# bms_slave.net
KiCad netlist of a schematic drawn in EAGLE
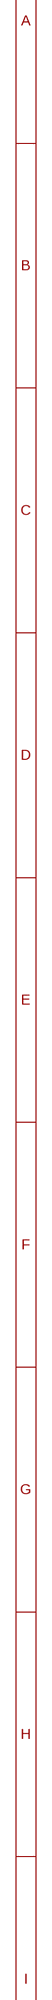
[diagram p0: schematic, sheet 1, part 1 of 2]
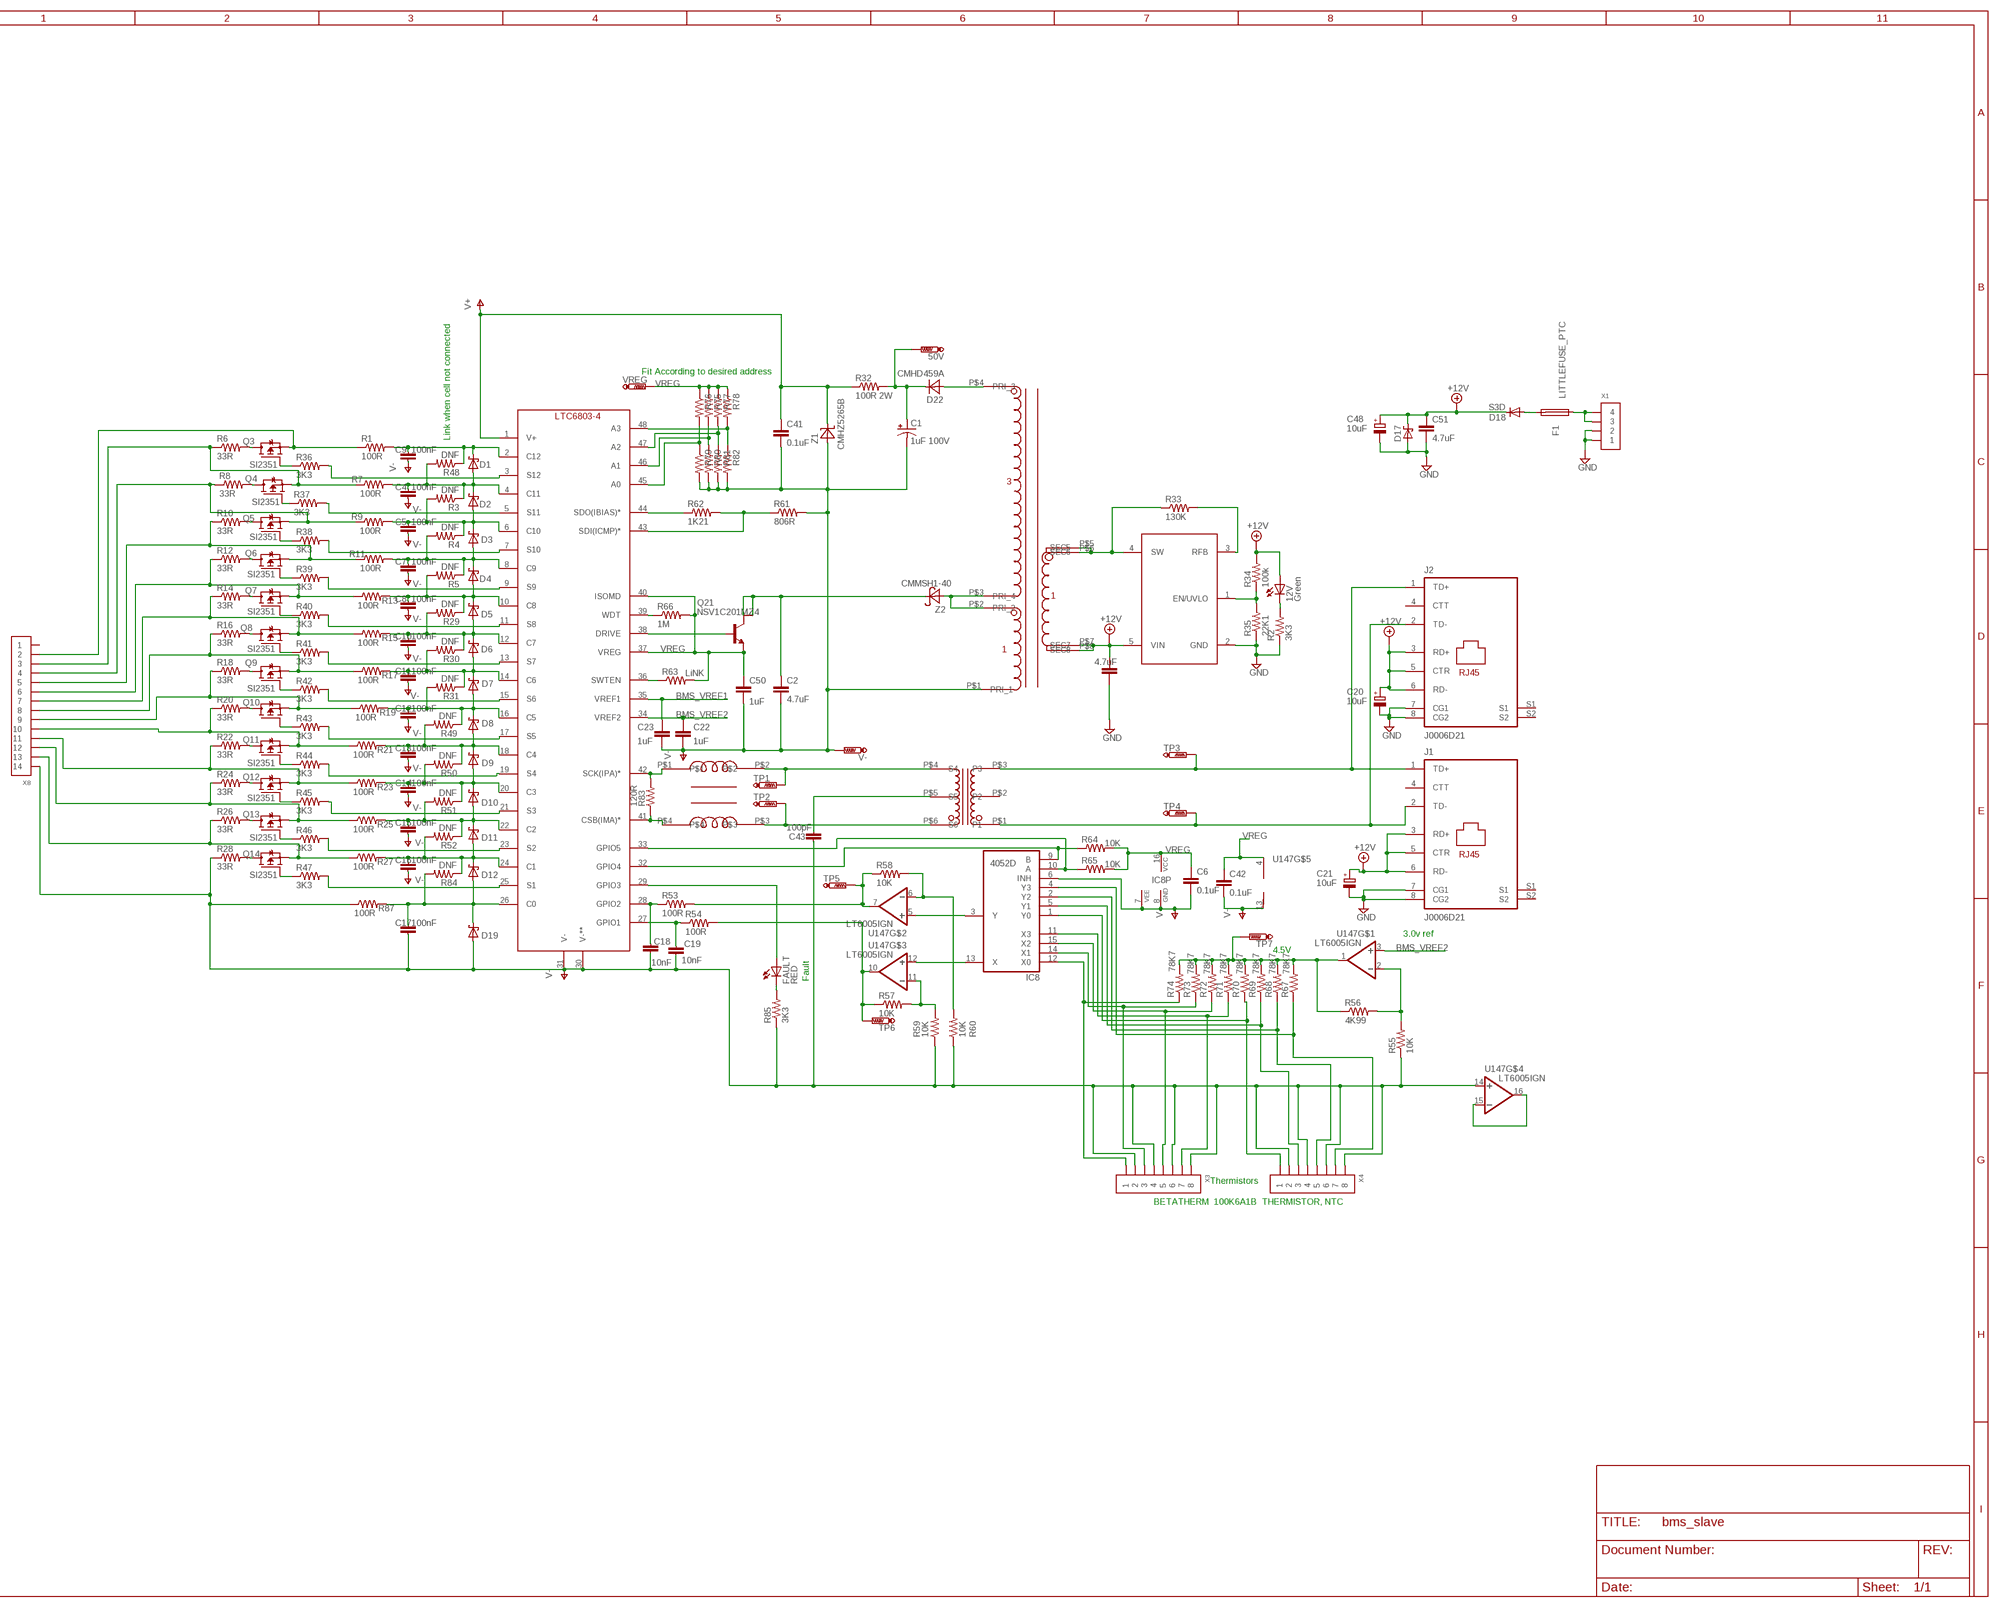
[diagram p1: schematic, sheet 1, part 2 of 2]

(export (version "E")
  (design (tool "Eeschema 10.0.6"))
  (components
    (comp (ref "12V")
      (value "Green")
      (footprint "eagle-import:CHIP-LED0805")
      (libsource (lib "eagle-import") (part "LEDCHIP-LED0805"))
    )
    (comp (ref "50V")
      (value "PTR1PAD1-13")
      (footprint "eagle-import:P1-13")
      (libsource (lib "eagle-import") (part "PTR1PAD1-13"))
    )
    (comp (ref "C1")
      (value "1uF 100V")
      (footprint "eagle-import:SMC_D")
      (libsource (lib "eagle-import") (part "CPOL-USSMCD"))
    )
    (comp (ref "C2")
      (value "4.7uF")
      (footprint "eagle-import:C1206")
      (libsource (lib "eagle-import") (part "C-EUC1206"))
    )
    (comp (ref "C3")
      (value "4.7uF")
      (footprint "eagle-import:C1206")
      (libsource (lib "eagle-import") (part "C-EUC1206"))
    )
    (comp (ref "C4")
      (value "100nF")
      (footprint "eagle-import:C0603@1")
      (libsource (lib "eagle-import") (part "C-EU-SMALL_0603"))
    )
    (comp (ref "C5")
      (value "100nF")
      (footprint "eagle-import:C0603@1")
      (libsource (lib "eagle-import") (part "C-EU-SMALL_0603"))
    )
    (comp (ref "C6")
      (value "0.1uF")
      (footprint "eagle-import:C1206")
      (libsource (lib "eagle-import") (part "C-EUC1206"))
    )
    (comp (ref "C7")
      (value "100nF")
      (footprint "eagle-import:C0603@1")
      (libsource (lib "eagle-import") (part "C-EU-SMALL_0603"))
    )
    (comp (ref "C8")
      (value "100nF")
      (footprint "eagle-import:C0603@1")
      (libsource (lib "eagle-import") (part "C-EU-SMALL_0603"))
    )
    (comp (ref "C9")
      (value "100nF")
      (footprint "eagle-import:C0603@1")
      (libsource (lib "eagle-import") (part "C-EU-SMALL_0603"))
    )
    (comp (ref "C10")
      (value "100nF")
      (footprint "eagle-import:C0603@1")
      (libsource (lib "eagle-import") (part "C-EU-SMALL_0603"))
    )
    (comp (ref "C11")
      (value "100nF")
      (footprint "eagle-import:C0603@1")
      (libsource (lib "eagle-import") (part "C-EU-SMALL_0603"))
    )
    (comp (ref "C12")
      (value "100nF")
      (footprint "eagle-import:C0603@1")
      (libsource (lib "eagle-import") (part "C-EU-SMALL_0603"))
    )
    (comp (ref "C13")
      (value "100nF")
      (footprint "eagle-import:C0603@1")
      (libsource (lib "eagle-import") (part "C-EU-SMALL_0603"))
    )
    (comp (ref "C14")
      (value "100nF")
      (footprint "eagle-import:C0603@1")
      (libsource (lib "eagle-import") (part "C-EU-SMALL_0603"))
    )
    (comp (ref "C15")
      (value "100nF")
      (footprint "eagle-import:C0603@1")
      (libsource (lib "eagle-import") (part "C-EU-SMALL_0603"))
    )
    (comp (ref "C16")
      (value "100nF")
      (footprint "eagle-import:C0603@1")
      (libsource (lib "eagle-import") (part "C-EU-SMALL_0603"))
    )
    (comp (ref "C17")
      (value "100nF")
      (footprint "eagle-import:C0603@1")
      (libsource (lib "eagle-import") (part "C-EU-SMALL_0603"))
    )
    (comp (ref "C18")
      (value "10nF")
      (footprint "eagle-import:C0603@1")
      (libsource (lib "eagle-import") (part "C-EU-SMALL_0603"))
    )
    (comp (ref "C19")
      (value "10nF")
      (footprint "eagle-import:C0603@1")
      (libsource (lib "eagle-import") (part "C-EU-SMALL_0603"))
    )
    (comp (ref "C20")
      (value "10uF")
      (footprint "eagle-import:SMC_D")
      (libsource (lib "eagle-import") (part "CPOL-EUSMCD"))
    )
    (comp (ref "C21")
      (value "10uF")
      (footprint "eagle-import:SMC_D")
      (libsource (lib "eagle-import") (part "CPOL-EUSMCD"))
    )
    (comp (ref "C22")
      (value "1uF")
      (footprint "eagle-import:C1206")
      (libsource (lib "eagle-import") (part "C-EUC1206"))
    )
    (comp (ref "C23")
      (value "1uF")
      (footprint "eagle-import:C1206")
      (libsource (lib "eagle-import") (part "C-EUC1206"))
    )
    (comp (ref "C41")
      (value "0.1uF")
      (footprint "eagle-import:C1206")
      (libsource (lib "eagle-import") (part "C-EUC1206"))
    )
    (comp (ref "C42")
      (value "0.1uF")
      (footprint "eagle-import:C1206")
      (libsource (lib "eagle-import") (part "C-EUC1206"))
    )
    (comp (ref "C43")
      (value "100pF")
      (footprint "eagle-import:C1206@1")
      (libsource (lib "eagle-import") (part "C-EU-SMALL"))
    )
    (comp (ref "C48")
      (value "10uF")
      (footprint "eagle-import:SMC_D")
      (libsource (lib "eagle-import") (part "CPOL-EUSMCD"))
    )
    (comp (ref "C50")
      (value "1uF")
      (footprint "eagle-import:C1206")
      (libsource (lib "eagle-import") (part "C-EUC1206"))
    )
    (comp (ref "C51")
      (value "4.7uF")
      (footprint "eagle-import:C1206")
      (libsource (lib "eagle-import") (part "C-EUC1206"))
    )
    (comp (ref "D1")
      (value "SMF5.0AT1")
      (footprint "eagle-import:SOD123FL")
      (libsource (lib "eagle-import") (part "SMF5.0AT1"))
    )
    (comp (ref "D2")
      (value "SMF5.0AT1")
      (footprint "eagle-import:SOD123FL")
      (libsource (lib "eagle-import") (part "SMF5.0AT1"))
    )
    (comp (ref "D3")
      (value "SMF5.0AT1")
      (footprint "eagle-import:SOD123FL")
      (libsource (lib "eagle-import") (part "SMF5.0AT1"))
    )
    (comp (ref "D4")
      (value "SMF5.0AT1")
      (footprint "eagle-import:SOD123FL")
      (libsource (lib "eagle-import") (part "SMF5.0AT1"))
    )
    (comp (ref "D5")
      (value "SMF5.0AT1")
      (footprint "eagle-import:SOD123FL")
      (libsource (lib "eagle-import") (part "SMF5.0AT1"))
    )
    (comp (ref "D6")
      (value "SMF5.0AT1")
      (footprint "eagle-import:SOD123FL")
      (libsource (lib "eagle-import") (part "SMF5.0AT1"))
    )
    (comp (ref "D7")
      (value "SMF5.0AT1")
      (footprint "eagle-import:SOD123FL")
      (libsource (lib "eagle-import") (part "SMF5.0AT1"))
    )
    (comp (ref "D8")
      (value "SMF5.0AT1")
      (footprint "eagle-import:SOD123FL")
      (libsource (lib "eagle-import") (part "SMF5.0AT1"))
    )
    (comp (ref "D9")
      (value "SMF5.0AT1")
      (footprint "eagle-import:SOD123FL")
      (libsource (lib "eagle-import") (part "SMF5.0AT1"))
    )
    (comp (ref "D10")
      (value "SMF5.0AT1")
      (footprint "eagle-import:SOD123FL")
      (libsource (lib "eagle-import") (part "SMF5.0AT1"))
    )
    (comp (ref "D11")
      (value "SMF5.0AT1")
      (footprint "eagle-import:SOD123FL")
      (libsource (lib "eagle-import") (part "SMF5.0AT1"))
    )
    (comp (ref "D12")
      (value "SMF5.0AT1")
      (footprint "eagle-import:SOD123FL")
      (libsource (lib "eagle-import") (part "SMF5.0AT1"))
    )
    (comp (ref "D17")
      (value "SCHOTTKY-DIODESMC")
      (footprint "eagle-import:SMC")
      (libsource (lib "eagle-import") (part "SCHOTTKY-DIODESMC"))
    )
    (comp (ref "D18")
      (value "S3D")
      (footprint "eagle-import:SMC")
      (libsource (lib "eagle-import") (part "DIODE-SMC"))
    )
    (comp (ref "D19")
      (value "SMF5.0AT1")
      (footprint "eagle-import:SOD123FL")
      (libsource (lib "eagle-import") (part "SMF5.0AT1"))
    )
    (comp (ref "D22")
      (value "CMHD459A")
      (footprint "eagle-import:SOD123")
      (libsource (lib "eagle-import") (part "CMHD459A"))
    )
    (comp (ref "F1")
      (value "LITTLEFUSE_PTC")
      (footprint "eagle-import:1812")
      (libsource (lib "eagle-import") (part "LITTLEFUSE_PTC"))
    )
    (comp (ref "FAULT")
      (value "RED")
      (footprint "eagle-import:CHIP-LED0805")
      (libsource (lib "eagle-import") (part "LEDCHIP-LED0805"))
    )
    (comp (ref "IC8")
      (value "4052D")
      (footprint "eagle-import:SO16")
      (libsource (lib "eagle-import") (part "4052D"))
    )
    (comp (ref "J1")
      (value "J0006D21")
      (footprint "eagle-import:J0-C_D_E")
      (libsource (lib "eagle-import") (part "J0006D21"))
    )
    (comp (ref "J2")
      (value "J0006D21")
      (footprint "eagle-import:J0-C_D_E")
      (libsource (lib "eagle-import") (part "J0006D21"))
    )
    (comp (ref "Q3")
      (value "SI2351")
      (footprint "eagle-import:SOT23")
      (libsource (lib "eagle-import") (part "SI2351"))
    )
    (comp (ref "Q4")
      (value "SI2351")
      (footprint "eagle-import:SOT23")
      (libsource (lib "eagle-import") (part "SI2351"))
    )
    (comp (ref "Q5")
      (value "SI2351")
      (footprint "eagle-import:SOT23")
      (libsource (lib "eagle-import") (part "SI2351"))
    )
    (comp (ref "Q6")
      (value "SI2351")
      (footprint "eagle-import:SOT23")
      (libsource (lib "eagle-import") (part "SI2351"))
    )
    (comp (ref "Q7")
      (value "SI2351")
      (footprint "eagle-import:SOT23")
      (libsource (lib "eagle-import") (part "SI2351"))
    )
    (comp (ref "Q8")
      (value "SI2351")
      (footprint "eagle-import:SOT23")
      (libsource (lib "eagle-import") (part "SI2351"))
    )
    (comp (ref "Q9")
      (value "SI2351")
      (footprint "eagle-import:SOT23")
      (libsource (lib "eagle-import") (part "SI2351"))
    )
    (comp (ref "Q10")
      (value "SI2351")
      (footprint "eagle-import:SOT23")
      (libsource (lib "eagle-import") (part "SI2351"))
    )
    (comp (ref "Q11")
      (value "SI2351")
      (footprint "eagle-import:SOT23")
      (libsource (lib "eagle-import") (part "SI2351"))
    )
    (comp (ref "Q12")
      (value "SI2351")
      (footprint "eagle-import:SOT23")
      (libsource (lib "eagle-import") (part "SI2351"))
    )
    (comp (ref "Q13")
      (value "SI2351")
      (footprint "eagle-import:SOT23")
      (libsource (lib "eagle-import") (part "SI2351"))
    )
    (comp (ref "Q14")
      (value "SI2351")
      (footprint "eagle-import:SOT23")
      (libsource (lib "eagle-import") (part "SI2351"))
    )
    (comp (ref "Q21")
      (value "NSV1C201MZ4")
      (footprint "eagle-import:SOT223")
      (libsource (lib "eagle-import") (part "NSV1C201MZ4"))
    )
    (comp (ref "R1")
      (value "100R")
      (footprint "eagle-import:R0603")
      (libsource (lib "eagle-import") (part "R-US_R0603"))
    )
    (comp (ref "R2")
      (value "3K3")
      (footprint "eagle-import:R0603")
      (libsource (lib "eagle-import") (part "R-US_R0603"))
    )
    (comp (ref "R3")
      (value "DNF")
      (footprint "eagle-import:R0603")
      (libsource (lib "eagle-import") (part "R-US_R0603"))
    )
    (comp (ref "R4")
      (value "DNF")
      (footprint "eagle-import:R0603")
      (libsource (lib "eagle-import") (part "R-US_R0603"))
    )
    (comp (ref "R5")
      (value "DNF")
      (footprint "eagle-import:R0603")
      (libsource (lib "eagle-import") (part "R-US_R0603"))
    )
    (comp (ref "R6")
      (value "33R")
      (footprint "eagle-import:R2512")
      (libsource (lib "eagle-import") (part "R-US_R2512"))
    )
    (comp (ref "R7")
      (value "100R")
      (footprint "eagle-import:R0603")
      (libsource (lib "eagle-import") (part "R-US_R0603"))
    )
    (comp (ref "R8")
      (value "33R")
      (footprint "eagle-import:R2512")
      (libsource (lib "eagle-import") (part "R-US_R2512"))
    )
    (comp (ref "R9")
      (value "100R")
      (footprint "eagle-import:R0603")
      (libsource (lib "eagle-import") (part "R-US_R0603"))
    )
    (comp (ref "R10")
      (value "33R")
      (footprint "eagle-import:R2512")
      (libsource (lib "eagle-import") (part "R-US_R2512"))
    )
    (comp (ref "R11")
      (value "100R")
      (footprint "eagle-import:R0603")
      (libsource (lib "eagle-import") (part "R-US_R0603"))
    )
    (comp (ref "R12")
      (value "33R")
      (footprint "eagle-import:R2512")
      (libsource (lib "eagle-import") (part "R-US_R2512"))
    )
    (comp (ref "R13")
      (value "100R")
      (footprint "eagle-import:R0603")
      (libsource (lib "eagle-import") (part "R-US_R0603"))
    )
    (comp (ref "R14")
      (value "33R")
      (footprint "eagle-import:R2512")
      (libsource (lib "eagle-import") (part "R-US_R2512"))
    )
    (comp (ref "R15")
      (value "100R")
      (footprint "eagle-import:R0603")
      (libsource (lib "eagle-import") (part "R-US_R0603"))
    )
    (comp (ref "R16")
      (value "33R")
      (footprint "eagle-import:R2512")
      (libsource (lib "eagle-import") (part "R-US_R2512"))
    )
    (comp (ref "R17")
      (value "100R")
      (footprint "eagle-import:R0603")
      (libsource (lib "eagle-import") (part "R-US_R0603"))
    )
    (comp (ref "R18")
      (value "33R")
      (footprint "eagle-import:R2512")
      (libsource (lib "eagle-import") (part "R-US_R2512"))
    )
    (comp (ref "R19")
      (value "100R")
      (footprint "eagle-import:R0603")
      (libsource (lib "eagle-import") (part "R-US_R0603"))
    )
    (comp (ref "R20")
      (value "33R")
      (footprint "eagle-import:R2512")
      (libsource (lib "eagle-import") (part "R-US_R2512"))
    )
    (comp (ref "R21")
      (value "100R")
      (footprint "eagle-import:R0603")
      (libsource (lib "eagle-import") (part "R-US_R0603"))
    )
    (comp (ref "R22")
      (value "33R")
      (footprint "eagle-import:R2512")
      (libsource (lib "eagle-import") (part "R-US_R2512"))
    )
    (comp (ref "R23")
      (value "100R")
      (footprint "eagle-import:R0603")
      (libsource (lib "eagle-import") (part "R-US_R0603"))
    )
    (comp (ref "R24")
      (value "33R")
      (footprint "eagle-import:R2512")
      (libsource (lib "eagle-import") (part "R-US_R2512"))
    )
    (comp (ref "R25")
      (value "100R")
      (footprint "eagle-import:R0603")
      (libsource (lib "eagle-import") (part "R-US_R0603"))
    )
    (comp (ref "R26")
      (value "33R")
      (footprint "eagle-import:R2512")
      (libsource (lib "eagle-import") (part "R-US_R2512"))
    )
    (comp (ref "R27")
      (value "100R")
      (footprint "eagle-import:R0603")
      (libsource (lib "eagle-import") (part "R-US_R0603"))
    )
    (comp (ref "R28")
      (value "33R")
      (footprint "eagle-import:R2512")
      (libsource (lib "eagle-import") (part "R-US_R2512"))
    )
    (comp (ref "R29")
      (value "DNF")
      (footprint "eagle-import:R0603")
      (libsource (lib "eagle-import") (part "R-US_R0603"))
    )
    (comp (ref "R30")
      (value "DNF")
      (footprint "eagle-import:R0603")
      (libsource (lib "eagle-import") (part "R-US_R0603"))
    )
    (comp (ref "R31")
      (value "DNF")
      (footprint "eagle-import:R0603")
      (libsource (lib "eagle-import") (part "R-US_R0603"))
    )
    (comp (ref "R32")
      (value "100R 2W")
      (footprint "eagle-import:R2512")
      (libsource (lib "eagle-import") (part "R-US_R2512"))
    )
    (comp (ref "R33")
      (value "130K")
      (footprint "eagle-import:R0603")
      (libsource (lib "eagle-import") (part "R-US_R0603"))
    )
    (comp (ref "R34")
      (value "100k")
      (footprint "eagle-import:R0603")
      (libsource (lib "eagle-import") (part "R-US_R0603"))
    )
    (comp (ref "R35")
      (value "22K1")
      (footprint "eagle-import:R0603")
      (libsource (lib "eagle-import") (part "R-US_R0603"))
    )
    (comp (ref "R36")
      (value "3K3")
      (footprint "eagle-import:R0603")
      (libsource (lib "eagle-import") (part "R-US_R0603"))
    )
    (comp (ref "R37")
      (value "3K3")
      (footprint "eagle-import:R0603")
      (libsource (lib "eagle-import") (part "R-US_R0603"))
    )
    (comp (ref "R38")
      (value "3K3")
      (footprint "eagle-import:R0603")
      (libsource (lib "eagle-import") (part "R-US_R0603"))
    )
    (comp (ref "R39")
      (value "3K3")
      (footprint "eagle-import:R0603")
      (libsource (lib "eagle-import") (part "R-US_R0603"))
    )
    (comp (ref "R40")
      (value "3K3")
      (footprint "eagle-import:R0603")
      (libsource (lib "eagle-import") (part "R-US_R0603"))
    )
    (comp (ref "R41")
      (value "3K3")
      (footprint "eagle-import:R0603")
      (libsource (lib "eagle-import") (part "R-US_R0603"))
    )
    (comp (ref "R42")
      (value "3K3")
      (footprint "eagle-import:R0603")
      (libsource (lib "eagle-import") (part "R-US_R0603"))
    )
    (comp (ref "R43")
      (value "3K3")
      (footprint "eagle-import:R0603")
      (libsource (lib "eagle-import") (part "R-US_R0603"))
    )
    (comp (ref "R44")
      (value "3K3")
      (footprint "eagle-import:R0603")
      (libsource (lib "eagle-import") (part "R-US_R0603"))
    )
    (comp (ref "R45")
      (value "3K3")
      (footprint "eagle-import:R0603")
      (libsource (lib "eagle-import") (part "R-US_R0603"))
    )
    (comp (ref "R46")
      (value "3K3")
      (footprint "eagle-import:R0603")
      (libsource (lib "eagle-import") (part "R-US_R0603"))
    )
    (comp (ref "R47")
      (value "3K3")
      (footprint "eagle-import:R0603")
      (libsource (lib "eagle-import") (part "R-US_R0603"))
    )
    (comp (ref "R48")
      (value "DNF")
      (footprint "eagle-import:R0603")
      (libsource (lib "eagle-import") (part "R-US_R0603"))
    )
    (comp (ref "R49")
      (value "DNF")
      (footprint "eagle-import:R0603")
      (libsource (lib "eagle-import") (part "R-US_R0603"))
    )
    (comp (ref "R50")
      (value "DNF")
      (footprint "eagle-import:R0603")
      (libsource (lib "eagle-import") (part "R-US_R0603"))
    )
    (comp (ref "R51")
      (value "DNF")
      (footprint "eagle-import:R0603")
      (libsource (lib "eagle-import") (part "R-US_R0603"))
    )
    (comp (ref "R52")
      (value "DNF")
      (footprint "eagle-import:R0603")
      (libsource (lib "eagle-import") (part "R-US_R0603"))
    )
    (comp (ref "R53")
      (value "100R")
      (footprint "eagle-import:R0603")
      (libsource (lib "eagle-import") (part "R-US_R0603"))
    )
    (comp (ref "R54")
      (value "100R")
      (footprint "eagle-import:R0603")
      (libsource (lib "eagle-import") (part "R-US_R0603"))
    )
    (comp (ref "R55")
      (value "10K")
      (footprint "eagle-import:R0603")
      (libsource (lib "eagle-import") (part "R-US_R0603"))
    )
    (comp (ref "R56")
      (value "4K99")
      (footprint "eagle-import:R0603")
      (libsource (lib "eagle-import") (part "R-US_R0603"))
    )
    (comp (ref "R57")
      (value "10K")
      (footprint "eagle-import:R0603")
      (libsource (lib "eagle-import") (part "R-US_R0603"))
    )
    (comp (ref "R58")
      (value "10K")
      (footprint "eagle-import:R0603")
      (libsource (lib "eagle-import") (part "R-US_R0603"))
    )
    (comp (ref "R59")
      (value "10K")
      (footprint "eagle-import:R0603")
      (libsource (lib "eagle-import") (part "R-US_R0603"))
    )
    (comp (ref "R60")
      (value "10K")
      (footprint "eagle-import:R0603")
      (libsource (lib "eagle-import") (part "R-US_R0603"))
    )
    (comp (ref "R61")
      (value "806R")
      (footprint "eagle-import:R0603")
      (libsource (lib "eagle-import") (part "R-US_R0603"))
    )
    (comp (ref "R62")
      (value "1K21")
      (footprint "eagle-import:R0603")
      (libsource (lib "eagle-import") (part "R-US_R0603"))
    )
    (comp (ref "R63")
      (value "LiNK")
      (footprint "eagle-import:R0603")
      (libsource (lib "eagle-import") (part "R-US_R0603"))
    )
    (comp (ref "R64")
      (value "10K")
      (footprint "eagle-import:R0603")
      (libsource (lib "eagle-import") (part "R-US_R0603"))
    )
    (comp (ref "R65")
      (value "10K")
      (footprint "eagle-import:R0603")
      (libsource (lib "eagle-import") (part "R-US_R0603"))
    )
    (comp (ref "R66")
      (value "1M")
      (footprint "eagle-import:R0603")
      (libsource (lib "eagle-import") (part "R-US_R0603"))
    )
    (comp (ref "R67")
      (value "78K7")
      (footprint "eagle-import:R0603")
      (libsource (lib "eagle-import") (part "R-US_R0603"))
    )
    (comp (ref "R68")
      (value "78K7")
      (footprint "eagle-import:R0603")
      (libsource (lib "eagle-import") (part "R-US_R0603"))
    )
    (comp (ref "R69")
      (value "78K7")
      (footprint "eagle-import:R0603")
      (libsource (lib "eagle-import") (part "R-US_R0603"))
    )
    (comp (ref "R70")
      (value "78K7")
      (footprint "eagle-import:R0603")
      (libsource (lib "eagle-import") (part "R-US_R0603"))
    )
    (comp (ref "R71")
      (value "78K7")
      (footprint "eagle-import:R0603")
      (libsource (lib "eagle-import") (part "R-US_R0603"))
    )
    (comp (ref "R72")
      (value "78K7")
      (footprint "eagle-import:R0603")
      (libsource (lib "eagle-import") (part "R-US_R0603"))
    )
    (comp (ref "R73")
      (value "78K7")
      (footprint "eagle-import:R0603")
      (libsource (lib "eagle-import") (part "R-US_R0603"))
    )
    (comp (ref "R74")
      (value "78K7")
      (footprint "eagle-import:R0603")
      (libsource (lib "eagle-import") (part "R-US_R0603"))
    )
    (comp (ref "R75")
      (value "R-US_R0603")
      (footprint "eagle-import:R0603")
      (libsource (lib "eagle-import") (part "R-US_R0603"))
    )
    (comp (ref "R76")
      (value "R-US_R0603")
      (footprint "eagle-import:R0603")
      (libsource (lib "eagle-import") (part "R-US_R0603"))
    )
    (comp (ref "R77")
      (value "R-US_R0603")
      (footprint "eagle-import:R0603")
      (libsource (lib "eagle-import") (part "R-US_R0603"))
    )
    (comp (ref "R78")
      (value "R-US_R0603")
      (footprint "eagle-import:R0603")
      (libsource (lib "eagle-import") (part "R-US_R0603"))
    )
    (comp (ref "R79")
      (value "R-US_R0603")
      (footprint "eagle-import:R0603")
      (libsource (lib "eagle-import") (part "R-US_R0603"))
    )
    (comp (ref "R80")
      (value "R-US_R0603")
      (footprint "eagle-import:R0603")
      (libsource (lib "eagle-import") (part "R-US_R0603"))
    )
    (comp (ref "R81")
      (value "R-US_R0603")
      (footprint "eagle-import:R0603")
      (libsource (lib "eagle-import") (part "R-US_R0603"))
    )
    (comp (ref "R82")
      (value "R-US_R0603")
      (footprint "eagle-import:R0603")
      (libsource (lib "eagle-import") (part "R-US_R0603"))
    )
    (comp (ref "R83")
      (value "120R")
      (footprint "eagle-import:R0603")
      (libsource (lib "eagle-import") (part "R-US_R0603"))
    )
    (comp (ref "R84")
      (value "DNF")
      (footprint "eagle-import:R0603")
      (libsource (lib "eagle-import") (part "R-US_R0603"))
    )
    (comp (ref "R85")
      (value "3K3")
      (footprint "eagle-import:R0603")
      (libsource (lib "eagle-import") (part "R-US_R0603"))
    )
    (comp (ref "R87")
      (value "100R")
      (footprint "eagle-import:R0603")
      (libsource (lib "eagle-import") (part "R-US_R0603"))
    )
    (comp (ref "TP1")
      (value "PTR1PAD1-13")
      (footprint "eagle-import:P1-13")
      (libsource (lib "eagle-import") (part "PTR1PAD1-13"))
    )
    (comp (ref "TP2")
      (value "PTR1PAD1-13")
      (footprint "eagle-import:P1-13")
      (libsource (lib "eagle-import") (part "PTR1PAD1-13"))
    )
    (comp (ref "TP3")
      (value "PTR1PAD1-13")
      (footprint "eagle-import:P1-13")
      (libsource (lib "eagle-import") (part "PTR1PAD1-13"))
    )
    (comp (ref "TP4")
      (value "PTR1PAD1-13")
      (footprint "eagle-import:P1-13")
      (libsource (lib "eagle-import") (part "PTR1PAD1-13"))
    )
    (comp (ref "TP5")
      (value "PTR1PAD1-13")
      (footprint "eagle-import:P1-13")
      (libsource (lib "eagle-import") (part "PTR1PAD1-13"))
    )
    (comp (ref "TP6")
      (value "PTR1PAD1-13")
      (footprint "eagle-import:P1-13")
      (libsource (lib "eagle-import") (part "PTR1PAD1-13"))
    )
    (comp (ref "TP7")
      (value "PTR1PAD1-13")
      (footprint "eagle-import:P1-13")
      (libsource (lib "eagle-import") (part "PTR1PAD1-13"))
    )
    (comp (ref "U$1")
      (value "DLW43SH510XK2")
      (footprint "eagle-import:DLW43S")
      (libsource (lib "eagle-import") (part "DLW43SH510XK2"))
    )
    (comp (ref "U$3")
      (value "T3001NL")
      (footprint "eagle-import:T3001NL")
      (libsource (lib "eagle-import") (part "T3001NL"))
    )
    (comp (ref "U$15")
      (value "WURTH_750370040")
      (footprint "eagle-import:WE_750370040")
      (libsource (lib "eagle-import") (part "WURTH_750370040"))
    )
    (comp (ref "U1")
      (value "LTC6804-2")
      (footprint "eagle-import:SSOP48")
      (libsource (lib "eagle-import") (part "LTC6804-2"))
    )
    (comp (ref "U21")
      (value "LT8300")
      (footprint "eagle-import:TSOT23-5")
      (libsource (lib "eagle-import") (part "LT8300"))
    )
    (comp (ref "U147")
      (value "LT6005IGN")
      (footprint "eagle-import:TSSOP16")
      (libsource (lib "eagle-import") (part "LT6005IGN"))
    )
    (comp (ref "V-")
      (value "PTR1PAD1-13")
      (footprint "eagle-import:P1-13")
      (libsource (lib "eagle-import") (part "PTR1PAD1-13"))
    )
    (comp (ref "VREG")
      (value "PTR1PAD1-13")
      (footprint "eagle-import:P1-13")
      (libsource (lib "eagle-import") (part "PTR1PAD1-13"))
    )
    (comp (ref "X1")
      (value "CONN_4-1-53261")
      (footprint "eagle-import:PB-53261-04")
      (libsource (lib "eagle-import") (part "CONN_4-1-53261"))
    )
    (comp (ref "X3")
      (value "CONN_8-1-53261")
      (footprint "eagle-import:PB-53261-08")
      (libsource (lib "eagle-import") (part "CONN_8-1-53261"))
    )
    (comp (ref "X4")
      (value "CONN_8-1-53261")
      (footprint "eagle-import:PB-53261-08")
      (libsource (lib "eagle-import") (part "CONN_8-1-53261"))
    )
    (comp (ref "X8")
      (value "CONN_14-1-53261")
      (footprint "eagle-import:PB-53261-14")
      (libsource (lib "eagle-import") (part "CONN_14-1-53261"))
    )
    (comp (ref "Z1")
      (value "CMHZ5265B")
      (footprint "eagle-import:SOD123")
      (libsource (lib "eagle-import") (part "CMHZ5265B"))
    )
    (comp (ref "Z2")
      (value "CMMSH1-40")
      (footprint "eagle-import:SOD123")
      (libsource (lib "eagle-import") (part "CMMSH1-40"))
    )
  )
  (nets
    (net (code "1") (name "+12V") (class "Default")
      (node (ref "12V") (pin "A") (pinfunction "A_A") (pintype "passive"))
      (node (ref "C20") (pin "+") (pinfunction "+_+") (pintype "passive"))
      (node (ref "C21") (pin "+") (pinfunction "+_+") (pintype "passive"))
      (node (ref "C3") (pin "1") (pinfunction "1_1") (pintype "passive"))
      (node (ref "C48") (pin "+") (pinfunction "+_+") (pintype "passive"))
      (node (ref "C51") (pin "1") (pinfunction "1_1") (pintype "passive"))
      (node (ref "D17") (pin "C") (pinfunction "C_C") (pintype "passive"))
      (node (ref "D18") (pin "C") (pinfunction "C_C") (pintype "passive"))
      (node (ref "J1") (pin "3") (pinfunction "RD+_3") (pintype "passive"))
      (node (ref "J1") (pin "5") (pinfunction "CTR_5") (pintype "passive"))
      (node (ref "J1") (pin "6") (pinfunction "RD-_6") (pintype "passive"))
      (node (ref "J2") (pin "3") (pinfunction "RD+_3") (pintype "passive"))
      (node (ref "J2") (pin "5") (pinfunction "CTR_5") (pintype "passive"))
      (node (ref "J2") (pin "6") (pinfunction "RD-_6") (pintype "passive"))
      (node (ref "R34") (pin "2") (pinfunction "2_2") (pintype "passive"))
      (node (ref "U$15") (pin "P$7") (pinfunction "SEC7_P$7") (pintype "bidirectional"))
      (node (ref "U$15") (pin "P$8") (pinfunction "SEC8_P$8") (pintype "bidirectional"))
      (node (ref "U21") (pin "5") (pinfunction "VIN_5") (pintype "bidirectional"))
    )
    (net (code "2") (name "/BMS_VREF1") (class "Default")
      (node (ref "C23") (pin "1") (pinfunction "1_1") (pintype "passive"))
      (node (ref "U1") (pin "35") (pinfunction "VREF1_35") (pintype "bidirectional"))
    )
    (net (code "3") (name "/BMS_VREF2") (class "Default")
      (node (ref "C22") (pin "1") (pinfunction "1_1") (pintype "passive"))
      (node (ref "U1") (pin "34") (pinfunction "VREF2_34") (pintype "bidirectional"))
      (node (ref "U147") (pin "3") (pinfunction "+IN_3") (pintype "input"))
    )
    (net (code "4") (name "/VREG") (class "Default")
      (node (ref "C42") (pin "1") (pinfunction "1_1") (pintype "passive"))
      (node (ref "C50") (pin "1") (pinfunction "1_1") (pintype "passive"))
      (node (ref "C6") (pin "1") (pinfunction "1_1") (pintype "passive"))
      (node (ref "IC8") (pin "16") (pinfunction "VCC_16") (pintype "power_in"))
      (node (ref "Q21") (pin "3") (pinfunction "E_3") (pintype "passive"))
      (node (ref "R63") (pin "2") (pinfunction "2_2") (pintype "passive"))
      (node (ref "R64") (pin "2") (pinfunction "2_2") (pintype "passive"))
      (node (ref "R65") (pin "2") (pinfunction "2_2") (pintype "passive"))
      (node (ref "R66") (pin "2") (pinfunction "2_2") (pintype "passive"))
      (node (ref "R75") (pin "1") (pinfunction "1_1") (pintype "passive"))
      (node (ref "R76") (pin "1") (pinfunction "1_1") (pintype "passive"))
      (node (ref "R77") (pin "1") (pinfunction "1_1") (pintype "passive"))
      (node (ref "R78") (pin "1") (pinfunction "1_1") (pintype "passive"))
      (node (ref "U1") (pin "37") (pinfunction "VREG_37") (pintype "power_in"))
      (node (ref "U1") (pin "40") (pinfunction "ISOMD_40") (pintype "bidirectional"))
      (node (ref "U147") (pin "4") (pinfunction "V+_4") (pintype "power_in"))
      (node (ref "VREG") (pin "TP") (pinfunction "TP_TP") (pintype "input"))
    )
    (net (code "5") (name "GND") (class "Default")
      (node (ref "C20") (pin "-") (pinfunction "-_-") (pintype "passive"))
      (node (ref "C21") (pin "-") (pinfunction "-_-") (pintype "passive"))
      (node (ref "C3") (pin "2") (pinfunction "2_2") (pintype "passive"))
      (node (ref "C48") (pin "-") (pinfunction "-_-") (pintype "passive"))
      (node (ref "C51") (pin "2") (pinfunction "2_2") (pintype "passive"))
      (node (ref "D17") (pin "A") (pinfunction "A_A") (pintype "passive"))
      (node (ref "J1") (pin "7") (pinfunction "CG1_7") (pintype "passive"))
      (node (ref "J1") (pin "8") (pinfunction "CG2_8") (pintype "passive"))
      (node (ref "J2") (pin "7") (pinfunction "CG1_7") (pintype "passive"))
      (node (ref "J2") (pin "8") (pinfunction "CG2_8") (pintype "passive"))
      (node (ref "R2") (pin "1") (pinfunction "1_1") (pintype "passive"))
      (node (ref "R35") (pin "1") (pinfunction "1_1") (pintype "passive"))
      (node (ref "U21") (pin "2") (pinfunction "GND_2") (pintype "power_in"))
      (node (ref "X1") (pin "1") (pinfunction "1_1") (pintype "bidirectional"))
      (node (ref "X1") (pin "2") (pinfunction "2_2") (pintype "bidirectional"))
    )
    (net (code "6") (name "Net-(12V-PadC)") (class "Default")
      (node (ref "12V") (pin "C") (pinfunction "C_C") (pintype "passive"))
      (node (ref "R2") (pin "2") (pinfunction "2_2") (pintype "passive"))
    )
    (net (code "7") (name "Net-(50V-PadTP)") (class "Default")
      (node (ref "50V") (pin "TP") (pinfunction "TP_TP") (pintype "input"))
      (node (ref "C1") (pin "+") (pinfunction "+_+") (pintype "passive"))
      (node (ref "D22") (pin "C") (pinfunction "C_C") (pintype "passive"))
      (node (ref "R32") (pin "2") (pinfunction "2_2") (pintype "passive"))
    )
    (net (code "8") (name "Net-(F1-1)") (class "Default")
      (node (ref "F1") (pin "P$1") (pinfunction "1_P$1") (pintype "passive"))
      (node (ref "X1") (pin "3") (pinfunction "3_3") (pintype "bidirectional"))
      (node (ref "X1") (pin "4") (pinfunction "4_4") (pintype "bidirectional"))
    )
    (net (code "9") (name "Net-(F1-2)") (class "Default")
      (node (ref "D18") (pin "A") (pinfunction "A_A") (pintype "passive"))
      (node (ref "F1") (pin "P$2") (pinfunction "2_P$2") (pintype "passive"))
    )
    (net (code "10") (name "Net-(FAULT-PadC)") (class "Default")
      (node (ref "FAULT") (pin "C") (pinfunction "C_C") (pintype "passive"))
      (node (ref "R85") (pin "2") (pinfunction "2_2") (pintype "passive"))
    )
    (net (code "11") (name "Net-(IC8A-A)") (class "Default")
      (node (ref "IC8") (pin "10") (pinfunction "A_10") (pintype "input"))
      (node (ref "R65") (pin "1") (pinfunction "1_1") (pintype "passive"))
      (node (ref "U1") (pin "33") (pinfunction "GPIO5_33") (pintype "bidirectional"))
    )
    (net (code "12") (name "Net-(IC8A-B)") (class "Default")
      (node (ref "IC8") (pin "9") (pinfunction "B_9") (pintype "input"))
      (node (ref "R64") (pin "1") (pinfunction "1_1") (pintype "passive"))
      (node (ref "U1") (pin "32") (pinfunction "GPIO4_32") (pintype "bidirectional"))
    )
    (net (code "13") (name "Net-(IC8A-X)") (class "Default")
      (node (ref "IC8") (pin "13") (pinfunction "X_13") (pintype "bidirectional"))
      (node (ref "U147") (pin "12") (pinfunction "+IN_12") (pintype "input"))
    )
    (net (code "14") (name "Net-(IC8A-X0)") (class "Default")
      (node (ref "IC8") (pin "12") (pinfunction "X0_12") (pintype "bidirectional"))
      (node (ref "R74") (pin "1") (pinfunction "1_1") (pintype "passive"))
      (node (ref "X3") (pin "1") (pinfunction "1_1") (pintype "bidirectional"))
    )
    (net (code "15") (name "Net-(IC8A-X1)") (class "Default")
      (node (ref "IC8") (pin "14") (pinfunction "X1_14") (pintype "bidirectional"))
      (node (ref "R73") (pin "1") (pinfunction "1_1") (pintype "passive"))
      (node (ref "X3") (pin "3") (pinfunction "3_3") (pintype "bidirectional"))
    )
    (net (code "16") (name "Net-(IC8A-X2)") (class "Default")
      (node (ref "IC8") (pin "15") (pinfunction "X2_15") (pintype "bidirectional"))
      (node (ref "R72") (pin "1") (pinfunction "1_1") (pintype "passive"))
      (node (ref "X3") (pin "5") (pinfunction "5_5") (pintype "bidirectional"))
    )
    (net (code "17") (name "Net-(IC8A-X3)") (class "Default")
      (node (ref "IC8") (pin "11") (pinfunction "X3_11") (pintype "bidirectional"))
      (node (ref "R71") (pin "1") (pinfunction "1_1") (pintype "passive"))
      (node (ref "X3") (pin "7") (pinfunction "7_7") (pintype "bidirectional"))
    )
    (net (code "18") (name "Net-(IC8A-Y)") (class "Default")
      (node (ref "IC8") (pin "3") (pinfunction "Y_3") (pintype "bidirectional"))
      (node (ref "U147") (pin "5") (pinfunction "+IN_5") (pintype "input"))
    )
    (net (code "19") (name "Net-(IC8A-Y0)") (class "Default")
      (node (ref "IC8") (pin "1") (pinfunction "Y0_1") (pintype "bidirectional"))
      (node (ref "R70") (pin "1") (pinfunction "1_1") (pintype "passive"))
      (node (ref "X4") (pin "1") (pinfunction "1_1") (pintype "bidirectional"))
    )
    (net (code "20") (name "Net-(IC8A-Y1)") (class "Default")
      (node (ref "IC8") (pin "5") (pinfunction "Y1_5") (pintype "bidirectional"))
      (node (ref "R69") (pin "1") (pinfunction "1_1") (pintype "passive"))
      (node (ref "X4") (pin "3") (pinfunction "3_3") (pintype "bidirectional"))
    )
    (net (code "21") (name "Net-(IC8A-Y2)") (class "Default")
      (node (ref "IC8") (pin "2") (pinfunction "Y2_2") (pintype "bidirectional"))
      (node (ref "R68") (pin "1") (pinfunction "1_1") (pintype "passive"))
      (node (ref "X4") (pin "5") (pinfunction "5_5") (pintype "bidirectional"))
    )
    (net (code "22") (name "Net-(IC8A-Y3)") (class "Default")
      (node (ref "IC8") (pin "4") (pinfunction "Y3_4") (pintype "bidirectional"))
      (node (ref "R67") (pin "1") (pinfunction "1_1") (pintype "passive"))
      (node (ref "X4") (pin "7") (pinfunction "7_7") (pintype "bidirectional"))
    )
    (net (code "23") (name "Net-(J1-TD+)") (class "Default")
      (node (ref "J1") (pin "1") (pinfunction "TD+_1") (pintype "passive"))
      (node (ref "J2") (pin "1") (pinfunction "TD+_1") (pintype "passive"))
      (node (ref "TP3") (pin "TP") (pinfunction "TP_TP") (pintype "input"))
      (node (ref "U$3") (pin "P$3") (pinfunction "P3_P$3") (pintype "bidirectional"))
    )
    (net (code "24") (name "Net-(J1-TD-)") (class "Default")
      (node (ref "J1") (pin "2") (pinfunction "TD-_2") (pintype "passive"))
      (node (ref "J2") (pin "2") (pinfunction "TD-_2") (pintype "passive"))
      (node (ref "TP4") (pin "TP") (pinfunction "TP_TP") (pintype "input"))
      (node (ref "U$3") (pin "P$1") (pinfunction "P1_P$1") (pintype "bidirectional"))
    )
    (net (code "25") (name "Net-(Q3-D)") (class "Default")
      (node (ref "Q3") (pin "3") (pinfunction "D_3") (pintype "passive"))
      (node (ref "R6") (pin "2") (pinfunction "2_2") (pintype "passive"))
    )
    (net (code "26") (name "Net-(Q3-G)") (class "Default")
      (node (ref "Q3") (pin "1") (pinfunction "G_1") (pintype "passive"))
      (node (ref "R36") (pin "1") (pinfunction "1_1") (pintype "passive"))
    )
    (net (code "27") (name "Net-(Q3-S)") (class "Default")
      (node (ref "Q3") (pin "2") (pinfunction "S_2") (pintype "passive"))
      (node (ref "R1") (pin "1") (pinfunction "1_1") (pintype "passive"))
      (node (ref "X8") (pin "2") (pinfunction "2_2") (pintype "bidirectional"))
    )
    (net (code "28") (name "Net-(Q4-D)") (class "Default")
      (node (ref "Q4") (pin "3") (pinfunction "D_3") (pintype "passive"))
      (node (ref "R8") (pin "2") (pinfunction "2_2") (pintype "passive"))
    )
    (net (code "29") (name "Net-(Q4-G)") (class "Default")
      (node (ref "Q4") (pin "1") (pinfunction "G_1") (pintype "passive"))
      (node (ref "R37") (pin "1") (pinfunction "1_1") (pintype "passive"))
    )
    (net (code "30") (name "Net-(Q4-S)") (class "Default")
      (node (ref "Q4") (pin "2") (pinfunction "S_2") (pintype "passive"))
      (node (ref "R6") (pin "1") (pinfunction "1_1") (pintype "passive"))
      (node (ref "R7") (pin "1") (pinfunction "1_1") (pintype "passive"))
      (node (ref "X8") (pin "3") (pinfunction "3_3") (pintype "bidirectional"))
    )
    (net (code "31") (name "Net-(Q5-D)") (class "Default")
      (node (ref "Q5") (pin "3") (pinfunction "D_3") (pintype "passive"))
      (node (ref "R10") (pin "2") (pinfunction "2_2") (pintype "passive"))
    )
    (net (code "32") (name "Net-(Q5-G)") (class "Default")
      (node (ref "Q5") (pin "1") (pinfunction "G_1") (pintype "passive"))
      (node (ref "R38") (pin "1") (pinfunction "1_1") (pintype "passive"))
    )
    (net (code "33") (name "Net-(Q5-S)") (class "Default")
      (node (ref "Q5") (pin "2") (pinfunction "S_2") (pintype "passive"))
      (node (ref "R8") (pin "1") (pinfunction "1_1") (pintype "passive"))
      (node (ref "R9") (pin "1") (pinfunction "1_1") (pintype "passive"))
      (node (ref "X8") (pin "4") (pinfunction "4_4") (pintype "bidirectional"))
    )
    (net (code "34") (name "Net-(Q6-D)") (class "Default")
      (node (ref "Q6") (pin "3") (pinfunction "D_3") (pintype "passive"))
      (node (ref "R12") (pin "2") (pinfunction "2_2") (pintype "passive"))
    )
    (net (code "35") (name "Net-(Q6-G)") (class "Default")
      (node (ref "Q6") (pin "1") (pinfunction "G_1") (pintype "passive"))
      (node (ref "R39") (pin "1") (pinfunction "1_1") (pintype "passive"))
    )
    (net (code "36") (name "Net-(Q6-S)") (class "Default")
      (node (ref "Q6") (pin "2") (pinfunction "S_2") (pintype "passive"))
      (node (ref "R10") (pin "1") (pinfunction "1_1") (pintype "passive"))
      (node (ref "R11") (pin "1") (pinfunction "1_1") (pintype "passive"))
      (node (ref "X8") (pin "5") (pinfunction "5_5") (pintype "bidirectional"))
    )
    (net (code "37") (name "Net-(Q7-D)") (class "Default")
      (node (ref "Q7") (pin "3") (pinfunction "D_3") (pintype "passive"))
      (node (ref "R14") (pin "2") (pinfunction "2_2") (pintype "passive"))
    )
    (net (code "38") (name "Net-(Q7-G)") (class "Default")
      (node (ref "Q7") (pin "1") (pinfunction "G_1") (pintype "passive"))
      (node (ref "R40") (pin "1") (pinfunction "1_1") (pintype "passive"))
    )
    (net (code "39") (name "Net-(Q7-S)") (class "Default")
      (node (ref "Q7") (pin "2") (pinfunction "S_2") (pintype "passive"))
      (node (ref "R12") (pin "1") (pinfunction "1_1") (pintype "passive"))
      (node (ref "R13") (pin "1") (pinfunction "1_1") (pintype "passive"))
      (node (ref "X8") (pin "6") (pinfunction "6_6") (pintype "bidirectional"))
    )
    (net (code "40") (name "Net-(Q8-D)") (class "Default")
      (node (ref "Q8") (pin "3") (pinfunction "D_3") (pintype "passive"))
      (node (ref "R16") (pin "2") (pinfunction "2_2") (pintype "passive"))
    )
    (net (code "41") (name "Net-(Q8-G)") (class "Default")
      (node (ref "Q8") (pin "1") (pinfunction "G_1") (pintype "passive"))
      (node (ref "R41") (pin "1") (pinfunction "1_1") (pintype "passive"))
    )
    (net (code "42") (name "Net-(Q8-S)") (class "Default")
      (node (ref "Q8") (pin "2") (pinfunction "S_2") (pintype "passive"))
      (node (ref "R14") (pin "1") (pinfunction "1_1") (pintype "passive"))
      (node (ref "R15") (pin "1") (pinfunction "1_1") (pintype "passive"))
      (node (ref "X8") (pin "7") (pinfunction "7_7") (pintype "bidirectional"))
    )
    (net (code "43") (name "Net-(Q9-D)") (class "Default")
      (node (ref "Q9") (pin "3") (pinfunction "D_3") (pintype "passive"))
      (node (ref "R18") (pin "2") (pinfunction "2_2") (pintype "passive"))
    )
    (net (code "44") (name "Net-(Q9-G)") (class "Default")
      (node (ref "Q9") (pin "1") (pinfunction "G_1") (pintype "passive"))
      (node (ref "R42") (pin "1") (pinfunction "1_1") (pintype "passive"))
    )
    (net (code "45") (name "Net-(Q9-S)") (class "Default")
      (node (ref "Q9") (pin "2") (pinfunction "S_2") (pintype "passive"))
      (node (ref "R16") (pin "1") (pinfunction "1_1") (pintype "passive"))
      (node (ref "R17") (pin "1") (pinfunction "1_1") (pintype "passive"))
      (node (ref "X8") (pin "8") (pinfunction "8_8") (pintype "bidirectional"))
    )
    (net (code "46") (name "Net-(Q10-D)") (class "Default")
      (node (ref "Q10") (pin "3") (pinfunction "D_3") (pintype "passive"))
      (node (ref "R20") (pin "2") (pinfunction "2_2") (pintype "passive"))
    )
    (net (code "47") (name "Net-(Q10-G)") (class "Default")
      (node (ref "Q10") (pin "1") (pinfunction "G_1") (pintype "passive"))
      (node (ref "R43") (pin "1") (pinfunction "1_1") (pintype "passive"))
    )
    (net (code "48") (name "Net-(Q10-S)") (class "Default")
      (node (ref "Q10") (pin "2") (pinfunction "S_2") (pintype "passive"))
      (node (ref "R18") (pin "1") (pinfunction "1_1") (pintype "passive"))
      (node (ref "R19") (pin "1") (pinfunction "1_1") (pintype "passive"))
      (node (ref "X8") (pin "9") (pinfunction "9_9") (pintype "bidirectional"))
    )
    (net (code "49") (name "Net-(Q11-D)") (class "Default")
      (node (ref "Q11") (pin "3") (pinfunction "D_3") (pintype "passive"))
      (node (ref "R22") (pin "2") (pinfunction "2_2") (pintype "passive"))
    )
    (net (code "50") (name "Net-(Q11-G)") (class "Default")
      (node (ref "Q11") (pin "1") (pinfunction "G_1") (pintype "passive"))
      (node (ref "R44") (pin "1") (pinfunction "1_1") (pintype "passive"))
    )
    (net (code "51") (name "Net-(Q11-S)") (class "Default")
      (node (ref "Q11") (pin "2") (pinfunction "S_2") (pintype "passive"))
      (node (ref "R20") (pin "1") (pinfunction "1_1") (pintype "passive"))
      (node (ref "R21") (pin "1") (pinfunction "1_1") (pintype "passive"))
      (node (ref "X8") (pin "10") (pinfunction "10_10") (pintype "bidirectional"))
    )
    (net (code "52") (name "Net-(Q12-D)") (class "Default")
      (node (ref "Q12") (pin "3") (pinfunction "D_3") (pintype "passive"))
      (node (ref "R24") (pin "2") (pinfunction "2_2") (pintype "passive"))
    )
    (net (code "53") (name "Net-(Q12-G)") (class "Default")
      (node (ref "Q12") (pin "1") (pinfunction "G_1") (pintype "passive"))
      (node (ref "R45") (pin "1") (pinfunction "1_1") (pintype "passive"))
    )
    (net (code "54") (name "Net-(Q12-S)") (class "Default")
      (node (ref "Q12") (pin "2") (pinfunction "S_2") (pintype "passive"))
      (node (ref "R22") (pin "1") (pinfunction "1_1") (pintype "passive"))
      (node (ref "R23") (pin "1") (pinfunction "1_1") (pintype "passive"))
      (node (ref "X8") (pin "11") (pinfunction "11_11") (pintype "bidirectional"))
    )
    (net (code "55") (name "Net-(Q13-D)") (class "Default")
      (node (ref "Q13") (pin "3") (pinfunction "D_3") (pintype "passive"))
      (node (ref "R26") (pin "2") (pinfunction "2_2") (pintype "passive"))
    )
    (net (code "56") (name "Net-(Q13-G)") (class "Default")
      (node (ref "Q13") (pin "1") (pinfunction "G_1") (pintype "passive"))
      (node (ref "R46") (pin "1") (pinfunction "1_1") (pintype "passive"))
    )
    (net (code "57") (name "Net-(Q13-S)") (class "Default")
      (node (ref "Q13") (pin "2") (pinfunction "S_2") (pintype "passive"))
      (node (ref "R24") (pin "1") (pinfunction "1_1") (pintype "passive"))
      (node (ref "R25") (pin "1") (pinfunction "1_1") (pintype "passive"))
      (node (ref "X8") (pin "12") (pinfunction "12_12") (pintype "bidirectional"))
    )
    (net (code "58") (name "Net-(Q14-D)") (class "Default")
      (node (ref "Q14") (pin "3") (pinfunction "D_3") (pintype "passive"))
      (node (ref "R28") (pin "2") (pinfunction "2_2") (pintype "passive"))
    )
    (net (code "59") (name "Net-(Q14-G)") (class "Default")
      (node (ref "Q14") (pin "1") (pinfunction "G_1") (pintype "passive"))
      (node (ref "R47") (pin "1") (pinfunction "1_1") (pintype "passive"))
    )
    (net (code "60") (name "Net-(Q14-S)") (class "Default")
      (node (ref "Q14") (pin "2") (pinfunction "S_2") (pintype "passive"))
      (node (ref "R26") (pin "1") (pinfunction "1_1") (pintype "passive"))
      (node (ref "R27") (pin "1") (pinfunction "1_1") (pintype "passive"))
      (node (ref "X8") (pin "13") (pinfunction "13_13") (pintype "bidirectional"))
    )
    (net (code "61") (name "Net-(Q21-B)") (class "Default")
      (node (ref "Q21") (pin "1") (pinfunction "B_1") (pintype "passive"))
      (node (ref "U1") (pin "38") (pinfunction "DRIVE_38") (pintype "bidirectional"))
    )
    (net (code "62") (name "Net-(Q21-C2)") (class "Default")
      (node (ref "C2") (pin "1") (pinfunction "1_1") (pintype "passive"))
      (node (ref "Q21") (pin "2") (pinfunction "C2_2") (pintype "passive"))
      (node (ref "Q21") (pin "4") (pinfunction "C4_4") (pintype "passive"))
      (node (ref "Z2") (pin "C") (pinfunction "C_C") (pintype "passive"))
    )
    (net (code "63") (name "Net-(U$3-S4)") (class "Default")
      (node (ref "TP1") (pin "TP") (pinfunction "TP_TP") (pintype "input"))
      (node (ref "U$1") (pin "P$2") (pinfunction "P$2_P$2") (pintype "bidirectional"))
      (node (ref "U$3") (pin "P$4") (pinfunction "S4_P$4") (pintype "bidirectional"))
    )
    (net (code "64") (name "Net-(U$3-S5)") (class "Default")
      (node (ref "C43") (pin "1") (pinfunction "1_1") (pintype "passive"))
      (node (ref "U$3") (pin "P$5") (pinfunction "S5_P$5") (pintype "bidirectional"))
    )
    (net (code "65") (name "Net-(U$3-S6)") (class "Default")
      (node (ref "TP2") (pin "TP") (pinfunction "TP_TP") (pintype "input"))
      (node (ref "U$1") (pin "P$3") (pinfunction "P$3_P$3") (pintype "bidirectional"))
      (node (ref "U$3") (pin "P$6") (pinfunction "S6_P$6") (pintype "bidirectional"))
    )
    (net (code "66") (name "Net-(U$15-PRI_2)") (class "Default")
      (node (ref "U$15") (pin "P$2") (pinfunction "PRI_2_P$2") (pintype "bidirectional"))
      (node (ref "U$15") (pin "P$3") (pinfunction "PRI_4_P$3") (pintype "bidirectional"))
      (node (ref "Z2") (pin "A") (pinfunction "A_A") (pintype "passive"))
    )
    (net (code "67") (name "Net-(U$15-PRI_3)") (class "Default")
      (node (ref "D22") (pin "A") (pinfunction "A_A") (pintype "passive"))
      (node (ref "U$15") (pin "P$4") (pinfunction "PRI_3_P$4") (pintype "bidirectional"))
    )
    (net (code "68") (name "Net-(U$15-SEC5)") (class "Default")
      (node (ref "R33") (pin "1") (pinfunction "1_1") (pintype "passive"))
      (node (ref "U$15") (pin "P$5") (pinfunction "SEC5_P$5") (pintype "bidirectional"))
      (node (ref "U$15") (pin "P$6") (pinfunction "SEC6_P$6") (pintype "bidirectional"))
      (node (ref "U21") (pin "4") (pinfunction "SW_4") (pintype "bidirectional"))
    )
    (net (code "69") (name "Net-(U1-A0)") (class "Default")
      (node (ref "R76") (pin "2") (pinfunction "2_2") (pintype "passive"))
      (node (ref "R79") (pin "1") (pinfunction "1_1") (pintype "passive"))
      (node (ref "U1") (pin "45") (pinfunction "A0_45") (pintype "bidirectional"))
    )
    (net (code "70") (name "Net-(U1-A1)") (class "Default")
      (node (ref "R75") (pin "2") (pinfunction "2_2") (pintype "passive"))
      (node (ref "R80") (pin "1") (pinfunction "1_1") (pintype "passive"))
      (node (ref "U1") (pin "46") (pinfunction "A1_46") (pintype "bidirectional"))
    )
    (net (code "71") (name "Net-(U1-A2)") (class "Default")
      (node (ref "R77") (pin "2") (pinfunction "2_2") (pintype "passive"))
      (node (ref "R81") (pin "1") (pinfunction "1_1") (pintype "passive"))
      (node (ref "U1") (pin "47") (pinfunction "A2_47") (pintype "bidirectional"))
    )
    (net (code "72") (name "Net-(U1-A3)") (class "Default")
      (node (ref "R78") (pin "2") (pinfunction "2_2") (pintype "passive"))
      (node (ref "R82") (pin "1") (pinfunction "1_1") (pintype "passive"))
      (node (ref "U1") (pin "48") (pinfunction "A3_48") (pintype "bidirectional"))
    )
    (net (code "73") (name "Net-(U1-C0)") (class "Default")
      (node (ref "C17") (pin "1") (pinfunction "1_1") (pintype "passive"))
      (node (ref "D12") (pin "A") (pinfunction "A_A") (pintype "passive"))
      (node (ref "D19") (pin "C") (pinfunction "C_C") (pintype "passive"))
      (node (ref "R84") (pin "2") (pinfunction "2_2") (pintype "passive"))
      (node (ref "R87") (pin "2") (pinfunction "2_2") (pintype "passive"))
      (node (ref "U1") (pin "26") (pinfunction "C0_26") (pintype "bidirectional"))
    )
    (net (code "74") (name "Net-(U1-C1)") (class "Default")
      (node (ref "C16") (pin "1") (pinfunction "1_1") (pintype "passive"))
      (node (ref "D11") (pin "A") (pinfunction "A_A") (pintype "passive"))
      (node (ref "D12") (pin "C") (pinfunction "C_C") (pintype "passive"))
      (node (ref "R27") (pin "2") (pinfunction "2_2") (pintype "passive"))
      (node (ref "R52") (pin "2") (pinfunction "2_2") (pintype "passive"))
      (node (ref "R84") (pin "1") (pinfunction "1_1") (pintype "passive"))
      (node (ref "U1") (pin "24") (pinfunction "C1_24") (pintype "bidirectional"))
    )
    (net (code "75") (name "Net-(U1-C2)") (class "Default")
      (node (ref "C15") (pin "1") (pinfunction "1_1") (pintype "passive"))
      (node (ref "D10") (pin "A") (pinfunction "A_A") (pintype "passive"))
      (node (ref "D11") (pin "C") (pinfunction "C_C") (pintype "passive"))
      (node (ref "R25") (pin "2") (pinfunction "2_2") (pintype "passive"))
      (node (ref "R51") (pin "2") (pinfunction "2_2") (pintype "passive"))
      (node (ref "R52") (pin "1") (pinfunction "1_1") (pintype "passive"))
      (node (ref "U1") (pin "22") (pinfunction "C2_22") (pintype "bidirectional"))
    )
    (net (code "76") (name "Net-(U1-C3)") (class "Default")
      (node (ref "C14") (pin "1") (pinfunction "1_1") (pintype "passive"))
      (node (ref "D10") (pin "C") (pinfunction "C_C") (pintype "passive"))
      (node (ref "D9") (pin "A") (pinfunction "A_A") (pintype "passive"))
      (node (ref "R23") (pin "2") (pinfunction "2_2") (pintype "passive"))
      (node (ref "R50") (pin "2") (pinfunction "2_2") (pintype "passive"))
      (node (ref "R51") (pin "1") (pinfunction "1_1") (pintype "passive"))
      (node (ref "U1") (pin "20") (pinfunction "C3_20") (pintype "bidirectional"))
    )
    (net (code "77") (name "Net-(U1-C4)") (class "Default")
      (node (ref "C13") (pin "1") (pinfunction "1_1") (pintype "passive"))
      (node (ref "D8") (pin "A") (pinfunction "A_A") (pintype "passive"))
      (node (ref "D9") (pin "C") (pinfunction "C_C") (pintype "passive"))
      (node (ref "R21") (pin "2") (pinfunction "2_2") (pintype "passive"))
      (node (ref "R49") (pin "2") (pinfunction "2_2") (pintype "passive"))
      (node (ref "R50") (pin "1") (pinfunction "1_1") (pintype "passive"))
      (node (ref "U1") (pin "18") (pinfunction "C4_18") (pintype "bidirectional"))
    )
    (net (code "78") (name "Net-(U1-C5)") (class "Default")
      (node (ref "C12") (pin "1") (pinfunction "1_1") (pintype "passive"))
      (node (ref "D7") (pin "A") (pinfunction "A_A") (pintype "passive"))
      (node (ref "D8") (pin "C") (pinfunction "C_C") (pintype "passive"))
      (node (ref "R19") (pin "2") (pinfunction "2_2") (pintype "passive"))
      (node (ref "R31") (pin "2") (pinfunction "2_2") (pintype "passive"))
      (node (ref "R49") (pin "1") (pinfunction "1_1") (pintype "passive"))
      (node (ref "U1") (pin "16") (pinfunction "C5_16") (pintype "bidirectional"))
    )
    (net (code "79") (name "Net-(U1-C6)") (class "Default")
      (node (ref "C11") (pin "1") (pinfunction "1_1") (pintype "passive"))
      (node (ref "D6") (pin "A") (pinfunction "A_A") (pintype "passive"))
      (node (ref "D7") (pin "C") (pinfunction "C_C") (pintype "passive"))
      (node (ref "R17") (pin "2") (pinfunction "2_2") (pintype "passive"))
      (node (ref "R30") (pin "2") (pinfunction "2_2") (pintype "passive"))
      (node (ref "R31") (pin "1") (pinfunction "1_1") (pintype "passive"))
      (node (ref "U1") (pin "14") (pinfunction "C6_14") (pintype "bidirectional"))
    )
    (net (code "80") (name "Net-(U1-C7)") (class "Default")
      (node (ref "C10") (pin "1") (pinfunction "1_1") (pintype "passive"))
      (node (ref "D5") (pin "A") (pinfunction "A_A") (pintype "passive"))
      (node (ref "D6") (pin "C") (pinfunction "C_C") (pintype "passive"))
      (node (ref "R15") (pin "2") (pinfunction "2_2") (pintype "passive"))
      (node (ref "R29") (pin "2") (pinfunction "2_2") (pintype "passive"))
      (node (ref "R30") (pin "1") (pinfunction "1_1") (pintype "passive"))
      (node (ref "U1") (pin "12") (pinfunction "C7_12") (pintype "bidirectional"))
    )
    (net (code "81") (name "Net-(U1-C8)") (class "Default")
      (node (ref "C8") (pin "1") (pinfunction "1_1") (pintype "passive"))
      (node (ref "D4") (pin "A") (pinfunction "A_A") (pintype "passive"))
      (node (ref "D5") (pin "C") (pinfunction "C_C") (pintype "passive"))
      (node (ref "R13") (pin "2") (pinfunction "2_2") (pintype "passive"))
      (node (ref "R29") (pin "1") (pinfunction "1_1") (pintype "passive"))
      (node (ref "R5") (pin "2") (pinfunction "2_2") (pintype "passive"))
      (node (ref "U1") (pin "10") (pinfunction "C8_10") (pintype "bidirectional"))
    )
    (net (code "82") (name "Net-(U1-C9)") (class "Default")
      (node (ref "C7") (pin "1") (pinfunction "1_1") (pintype "passive"))
      (node (ref "D3") (pin "A") (pinfunction "A_A") (pintype "passive"))
      (node (ref "D4") (pin "C") (pinfunction "C_C") (pintype "passive"))
      (node (ref "R11") (pin "2") (pinfunction "2_2") (pintype "passive"))
      (node (ref "R4") (pin "2") (pinfunction "2_2") (pintype "passive"))
      (node (ref "R5") (pin "1") (pinfunction "1_1") (pintype "passive"))
      (node (ref "U1") (pin "8") (pinfunction "C9_8") (pintype "bidirectional"))
    )
    (net (code "83") (name "Net-(U1-C10)") (class "Default")
      (node (ref "C5") (pin "1") (pinfunction "1_1") (pintype "passive"))
      (node (ref "D2") (pin "A") (pinfunction "A_A") (pintype "passive"))
      (node (ref "D3") (pin "C") (pinfunction "C_C") (pintype "passive"))
      (node (ref "R3") (pin "2") (pinfunction "2_2") (pintype "passive"))
      (node (ref "R4") (pin "1") (pinfunction "1_1") (pintype "passive"))
      (node (ref "R9") (pin "2") (pinfunction "2_2") (pintype "passive"))
      (node (ref "U1") (pin "6") (pinfunction "C10_6") (pintype "bidirectional"))
    )
    (net (code "84") (name "Net-(U1-C11)") (class "Default")
      (node (ref "C4") (pin "1") (pinfunction "1_1") (pintype "passive"))
      (node (ref "D1") (pin "A") (pinfunction "A_A") (pintype "passive"))
      (node (ref "D2") (pin "C") (pinfunction "C_C") (pintype "passive"))
      (node (ref "R3") (pin "1") (pinfunction "1_1") (pintype "passive"))
      (node (ref "R48") (pin "2") (pinfunction "2_2") (pintype "passive"))
      (node (ref "R7") (pin "2") (pinfunction "2_2") (pintype "passive"))
      (node (ref "U1") (pin "4") (pinfunction "C11_4") (pintype "bidirectional"))
    )
    (net (code "85") (name "Net-(U1-C12)") (class "Default")
      (node (ref "C9") (pin "1") (pinfunction "1_1") (pintype "passive"))
      (node (ref "D1") (pin "C") (pinfunction "C_C") (pintype "passive"))
      (node (ref "R1") (pin "2") (pinfunction "2_2") (pintype "passive"))
      (node (ref "R48") (pin "1") (pinfunction "1_1") (pintype "passive"))
      (node (ref "U1") (pin "2") (pinfunction "C12_2") (pintype "bidirectional"))
    )
    (net (code "86") (name "Net-(U1-CSB(IMA)*)") (class "Default")
      (node (ref "R83") (pin "1") (pinfunction "1_1") (pintype "passive"))
      (node (ref "U$1") (pin "P$4") (pinfunction "P$4_P$4") (pintype "bidirectional"))
      (node (ref "U1") (pin "41") (pinfunction "CSB(IMA)*_41") (pintype "bidirectional"))
    )
    (net (code "87") (name "Net-(U1-GPIO1)") (class "Default")
      (node (ref "C19") (pin "1") (pinfunction "1_1") (pintype "passive"))
      (node (ref "R54") (pin "1") (pinfunction "1_1") (pintype "passive"))
      (node (ref "U1") (pin "27") (pinfunction "GPIO1_27") (pintype "bidirectional"))
    )
    (net (code "88") (name "Net-(U1-GPIO2)") (class "Default")
      (node (ref "C18") (pin "1") (pinfunction "1_1") (pintype "passive"))
      (node (ref "R53") (pin "1") (pinfunction "1_1") (pintype "passive"))
      (node (ref "U1") (pin "28") (pinfunction "GPIO2_28") (pintype "bidirectional"))
    )
    (net (code "89") (name "Net-(U1-GPIO3)") (class "Default")
      (node (ref "FAULT") (pin "A") (pinfunction "A_A") (pintype "passive"))
      (node (ref "U1") (pin "29") (pinfunction "GPIO3_29") (pintype "bidirectional"))
    )
    (net (code "90") (name "Net-(U1-S1)") (class "Default")
      (node (ref "R47") (pin "2") (pinfunction "2_2") (pintype "passive"))
      (node (ref "U1") (pin "25") (pinfunction "S1_25") (pintype "bidirectional"))
    )
    (net (code "91") (name "Net-(U1-S2)") (class "Default")
      (node (ref "R46") (pin "2") (pinfunction "2_2") (pintype "passive"))
      (node (ref "U1") (pin "23") (pinfunction "S2_23") (pintype "bidirectional"))
    )
    (net (code "92") (name "Net-(U1-S3)") (class "Default")
      (node (ref "R45") (pin "2") (pinfunction "2_2") (pintype "passive"))
      (node (ref "U1") (pin "21") (pinfunction "S3_21") (pintype "bidirectional"))
    )
    (net (code "93") (name "Net-(U1-S4)") (class "Default")
      (node (ref "R44") (pin "2") (pinfunction "2_2") (pintype "passive"))
      (node (ref "U1") (pin "19") (pinfunction "S4_19") (pintype "bidirectional"))
    )
    (net (code "94") (name "Net-(U1-S5)") (class "Default")
      (node (ref "R43") (pin "2") (pinfunction "2_2") (pintype "passive"))
      (node (ref "U1") (pin "17") (pinfunction "S5_17") (pintype "bidirectional"))
    )
    (net (code "95") (name "Net-(U1-S6)") (class "Default")
      (node (ref "R42") (pin "2") (pinfunction "2_2") (pintype "passive"))
      (node (ref "U1") (pin "15") (pinfunction "S6_15") (pintype "bidirectional"))
    )
    (net (code "96") (name "Net-(U1-S7)") (class "Default")
      (node (ref "R41") (pin "2") (pinfunction "2_2") (pintype "passive"))
      (node (ref "U1") (pin "13") (pinfunction "S7_13") (pintype "bidirectional"))
    )
    (net (code "97") (name "Net-(U1-S8)") (class "Default")
      (node (ref "R40") (pin "2") (pinfunction "2_2") (pintype "passive"))
      (node (ref "U1") (pin "11") (pinfunction "S8_11") (pintype "bidirectional"))
    )
    (net (code "98") (name "Net-(U1-S9)") (class "Default")
      (node (ref "R39") (pin "2") (pinfunction "2_2") (pintype "passive"))
      (node (ref "U1") (pin "9") (pinfunction "S9_9") (pintype "bidirectional"))
    )
    (net (code "99") (name "Net-(U1-S10)") (class "Default")
      (node (ref "R38") (pin "2") (pinfunction "2_2") (pintype "passive"))
      (node (ref "U1") (pin "7") (pinfunction "S10_7") (pintype "bidirectional"))
    )
    (net (code "100") (name "Net-(U1-S11)") (class "Default")
      (node (ref "R37") (pin "2") (pinfunction "2_2") (pintype "passive"))
      (node (ref "U1") (pin "5") (pinfunction "S11_5") (pintype "bidirectional"))
    )
    (net (code "101") (name "Net-(U1-S12)") (class "Default")
      (node (ref "R36") (pin "2") (pinfunction "2_2") (pintype "passive"))
      (node (ref "U1") (pin "3") (pinfunction "S12_3") (pintype "bidirectional"))
    )
    (net (code "102") (name "Net-(U1-SCK(IPA)*)") (class "Default")
      (node (ref "R83") (pin "2") (pinfunction "2_2") (pintype "passive"))
      (node (ref "U$1") (pin "P$1") (pinfunction "P$1_P$1") (pintype "bidirectional"))
      (node (ref "U1") (pin "42") (pinfunction "SCK(IPA)*_42") (pintype "bidirectional"))
    )
    (net (code "103") (name "Net-(U1-SDI(ICMP)*)") (class "Default")
      (node (ref "R61") (pin "1") (pinfunction "1_1") (pintype "passive"))
      (node (ref "R62") (pin "2") (pinfunction "2_2") (pintype "passive"))
      (node (ref "U1") (pin "43") (pinfunction "SDI(ICMP)*_43") (pintype "bidirectional"))
    )
    (net (code "104") (name "Net-(U1-SDO(IBIAS)*)") (class "Default")
      (node (ref "R62") (pin "1") (pinfunction "1_1") (pintype "passive"))
      (node (ref "U1") (pin "44") (pinfunction "SDO(IBIAS)*_44") (pintype "bidirectional"))
    )
    (net (code "105") (name "Net-(U1-SWTEN)") (class "Default")
      (node (ref "R63") (pin "1") (pinfunction "1_1") (pintype "passive"))
      (node (ref "U1") (pin "36") (pinfunction "SWTEN_36") (pintype "bidirectional"))
    )
    (net (code "106") (name "Net-(U1-WDT)") (class "Default")
      (node (ref "R66") (pin "1") (pinfunction "1_1") (pintype "passive"))
      (node (ref "U1") (pin "39") (pinfunction "WDT_39") (pintype "bidirectional"))
    )
    (net (code "107") (name "Net-(U21-EN{slash}UVLO)") (class "Default")
      (node (ref "R34") (pin "1") (pinfunction "1_1") (pintype "passive"))
      (node (ref "R35") (pin "2") (pinfunction "2_2") (pintype "passive"))
      (node (ref "U21") (pin "1") (pinfunction "EN/UVLO_1") (pintype "bidirectional"))
    )
    (net (code "108") (name "Net-(U21-RFB)") (class "Default")
      (node (ref "R33") (pin "2") (pinfunction "2_2") (pintype "passive"))
      (node (ref "U21") (pin "3") (pinfunction "RFB_3") (pintype "bidirectional"))
    )
    (net (code "109") (name "Net-(U147A--IN)") (class "Default")
      (node (ref "R55") (pin "2") (pinfunction "2_2") (pintype "passive"))
      (node (ref "R56") (pin "2") (pinfunction "2_2") (pintype "passive"))
      (node (ref "U147") (pin "2") (pinfunction "-IN_2") (pintype "input"))
    )
    (net (code "110") (name "Net-(U147A-OUT)") (class "Default")
      (node (ref "R56") (pin "1") (pinfunction "1_1") (pintype "passive"))
      (node (ref "R67") (pin "2") (pinfunction "2_2") (pintype "passive"))
      (node (ref "R68") (pin "2") (pinfunction "2_2") (pintype "passive"))
      (node (ref "R69") (pin "2") (pinfunction "2_2") (pintype "passive"))
      (node (ref "R70") (pin "2") (pinfunction "2_2") (pintype "passive"))
      (node (ref "R71") (pin "2") (pinfunction "2_2") (pintype "passive"))
      (node (ref "R72") (pin "2") (pinfunction "2_2") (pintype "passive"))
      (node (ref "R73") (pin "2") (pinfunction "2_2") (pintype "passive"))
      (node (ref "R74") (pin "2") (pinfunction "2_2") (pintype "passive"))
      (node (ref "TP7") (pin "TP") (pinfunction "TP_TP") (pintype "input"))
      (node (ref "U147") (pin "1") (pinfunction "OUT_1") (pintype "output"))
    )
    (net (code "111") (name "Net-(U147B--IN)") (class "Default")
      (node (ref "R58") (pin "2") (pinfunction "2_2") (pintype "passive"))
      (node (ref "R60") (pin "2") (pinfunction "2_2") (pintype "passive"))
      (node (ref "U147") (pin "6") (pinfunction "-IN_6") (pintype "input"))
    )
    (net (code "112") (name "Net-(U147B-OUT)") (class "Default")
      (node (ref "R53") (pin "2") (pinfunction "2_2") (pintype "passive"))
      (node (ref "R58") (pin "1") (pinfunction "1_1") (pintype "passive"))
      (node (ref "TP5") (pin "TP") (pinfunction "TP_TP") (pintype "input"))
      (node (ref "U147") (pin "7") (pinfunction "OUT_7") (pintype "output"))
    )
    (net (code "113") (name "Net-(U147C--IN)") (class "Default")
      (node (ref "R57") (pin "2") (pinfunction "2_2") (pintype "passive"))
      (node (ref "R59") (pin "2") (pinfunction "2_2") (pintype "passive"))
      (node (ref "U147") (pin "11") (pinfunction "-IN_11") (pintype "input"))
    )
    (net (code "114") (name "Net-(U147C-OUT)") (class "Default")
      (node (ref "R54") (pin "2") (pinfunction "2_2") (pintype "passive"))
      (node (ref "R57") (pin "1") (pinfunction "1_1") (pintype "passive"))
      (node (ref "TP6") (pin "TP") (pinfunction "TP_TP") (pintype "input"))
      (node (ref "U147") (pin "10") (pinfunction "OUT_10") (pintype "output"))
    )
    (net (code "115") (name "Net-(U147D--IN)") (class "Default")
      (node (ref "U147") (pin "15") (pinfunction "-IN_15") (pintype "input"))
      (node (ref "U147") (pin "16") (pinfunction "OUT_16") (pintype "output"))
    )
    (net (code "116") (name "V+") (class "Default")
      (node (ref "C41") (pin "1") (pinfunction "1_1") (pintype "passive"))
      (node (ref "R32") (pin "1") (pinfunction "1_1") (pintype "passive"))
      (node (ref "U1") (pin "1") (pinfunction "V+_1") (pintype "power_in"))
      (node (ref "Z1") (pin "C") (pinfunction "C_C") (pintype "passive"))
    )
    (net (code "117") (name "V-") (class "Default")
      (node (ref "C1") (pin "-") (pinfunction "-_-") (pintype "passive"))
      (node (ref "C10") (pin "2") (pinfunction "2_2") (pintype "passive"))
      (node (ref "C11") (pin "2") (pinfunction "2_2") (pintype "passive"))
      (node (ref "C12") (pin "2") (pinfunction "2_2") (pintype "passive"))
      (node (ref "C13") (pin "2") (pinfunction "2_2") (pintype "passive"))
      (node (ref "C14") (pin "2") (pinfunction "2_2") (pintype "passive"))
      (node (ref "C15") (pin "2") (pinfunction "2_2") (pintype "passive"))
      (node (ref "C16") (pin "2") (pinfunction "2_2") (pintype "passive"))
      (node (ref "C17") (pin "2") (pinfunction "2_2") (pintype "passive"))
      (node (ref "C18") (pin "2") (pinfunction "2_2") (pintype "passive"))
      (node (ref "C19") (pin "2") (pinfunction "2_2") (pintype "passive"))
      (node (ref "C2") (pin "2") (pinfunction "2_2") (pintype "passive"))
      (node (ref "C22") (pin "2") (pinfunction "2_2") (pintype "passive"))
      (node (ref "C23") (pin "2") (pinfunction "2_2") (pintype "passive"))
      (node (ref "C4") (pin "2") (pinfunction "2_2") (pintype "passive"))
      (node (ref "C41") (pin "2") (pinfunction "2_2") (pintype "passive"))
      (node (ref "C42") (pin "2") (pinfunction "2_2") (pintype "passive"))
      (node (ref "C43") (pin "2") (pinfunction "2_2") (pintype "passive"))
      (node (ref "C5") (pin "2") (pinfunction "2_2") (pintype "passive"))
      (node (ref "C50") (pin "2") (pinfunction "2_2") (pintype "passive"))
      (node (ref "C6") (pin "2") (pinfunction "2_2") (pintype "passive"))
      (node (ref "C7") (pin "2") (pinfunction "2_2") (pintype "passive"))
      (node (ref "C8") (pin "2") (pinfunction "2_2") (pintype "passive"))
      (node (ref "C9") (pin "2") (pinfunction "2_2") (pintype "passive"))
      (node (ref "D19") (pin "A") (pinfunction "A_A") (pintype "passive"))
      (node (ref "IC8") (pin "6") (pinfunction "INH_6") (pintype "input"))
      (node (ref "IC8") (pin "7") (pinfunction "VEE_7") (pintype "power_in"))
      (node (ref "IC8") (pin "8") (pinfunction "GND_8") (pintype "power_in"))
      (node (ref "R28") (pin "1") (pinfunction "1_1") (pintype "passive"))
      (node (ref "R55") (pin "1") (pinfunction "1_1") (pintype "passive"))
      (node (ref "R59") (pin "1") (pinfunction "1_1") (pintype "passive"))
      (node (ref "R60") (pin "1") (pinfunction "1_1") (pintype "passive"))
      (node (ref "R61") (pin "2") (pinfunction "2_2") (pintype "passive"))
      (node (ref "R79") (pin "2") (pinfunction "2_2") (pintype "passive"))
      (node (ref "R80") (pin "2") (pinfunction "2_2") (pintype "passive"))
      (node (ref "R81") (pin "2") (pinfunction "2_2") (pintype "passive"))
      (node (ref "R82") (pin "2") (pinfunction "2_2") (pintype "passive"))
      (node (ref "R85") (pin "1") (pinfunction "1_1") (pintype "passive"))
      (node (ref "R87") (pin "1") (pinfunction "1_1") (pintype "passive"))
      (node (ref "U$15") (pin "P$1") (pinfunction "PRI_1_P$1") (pintype "bidirectional"))
      (node (ref "U1") (pin "30") (pinfunction "V-**_30") (pintype "bidirectional"))
      (node (ref "U1") (pin "31") (pinfunction "V-_31") (pintype "power_in"))
      (node (ref "U147") (pin "13") (pinfunction "V-_13") (pintype "power_in"))
      (node (ref "U147") (pin "14") (pinfunction "+IN_14") (pintype "input"))
      (node (ref "V-") (pin "TP") (pinfunction "TP_TP") (pintype "input"))
      (node (ref "X3") (pin "2") (pinfunction "2_2") (pintype "bidirectional"))
      (node (ref "X3") (pin "4") (pinfunction "4_4") (pintype "bidirectional"))
      (node (ref "X3") (pin "6") (pinfunction "6_6") (pintype "bidirectional"))
      (node (ref "X3") (pin "8") (pinfunction "8_8") (pintype "bidirectional"))
      (node (ref "X4") (pin "2") (pinfunction "2_2") (pintype "bidirectional"))
      (node (ref "X4") (pin "4") (pinfunction "4_4") (pintype "bidirectional"))
      (node (ref "X4") (pin "6") (pinfunction "6_6") (pintype "bidirectional"))
      (node (ref "X4") (pin "8") (pinfunction "8_8") (pintype "bidirectional"))
      (node (ref "X8") (pin "14") (pinfunction "14_14") (pintype "bidirectional"))
      (node (ref "Z1") (pin "A") (pinfunction "A_A") (pintype "passive"))
    )
    (net (code "118") (name "unconnected-(J1-CTT-Pad4)") (class "Default")
      (node (ref "J1") (pin "4") (pinfunction "CTT_4") (pintype "passive"))
    )
    (net (code "119") (name "unconnected-(J1-PadS1)") (class "Default")
      (node (ref "J1") (pin "S1") (pinfunction "S1_S1") (pintype "passive"))
    )
    (net (code "120") (name "unconnected-(J1-PadS2)") (class "Default")
      (node (ref "J1") (pin "S2") (pinfunction "S2_S2") (pintype "passive"))
    )
    (net (code "121") (name "unconnected-(J2-CTT-Pad4)") (class "Default")
      (node (ref "J2") (pin "4") (pinfunction "CTT_4") (pintype "passive"))
    )
    (net (code "122") (name "unconnected-(J2-PadS1)") (class "Default")
      (node (ref "J2") (pin "S1") (pinfunction "S1_S1") (pintype "passive"))
    )
    (net (code "123") (name "unconnected-(J2-PadS2)") (class "Default")
      (node (ref "J2") (pin "S2") (pinfunction "S2_S2") (pintype "passive"))
    )
    (net (code "124") (name "unconnected-(U$3-P2-PadP$2)") (class "Default")
      (node (ref "U$3") (pin "P$2") (pinfunction "P2_P$2") (pintype "bidirectional"))
    )
    (net (code "125") (name "unconnected-(X8-Pad1)") (class "Default")
      (node (ref "X8") (pin "1") (pinfunction "1_1") (pintype "bidirectional"))
    )
  )
)
